# GB202-CC-from-SF-Base.net
KiCad netlist of a schematic drawn in EAGLE
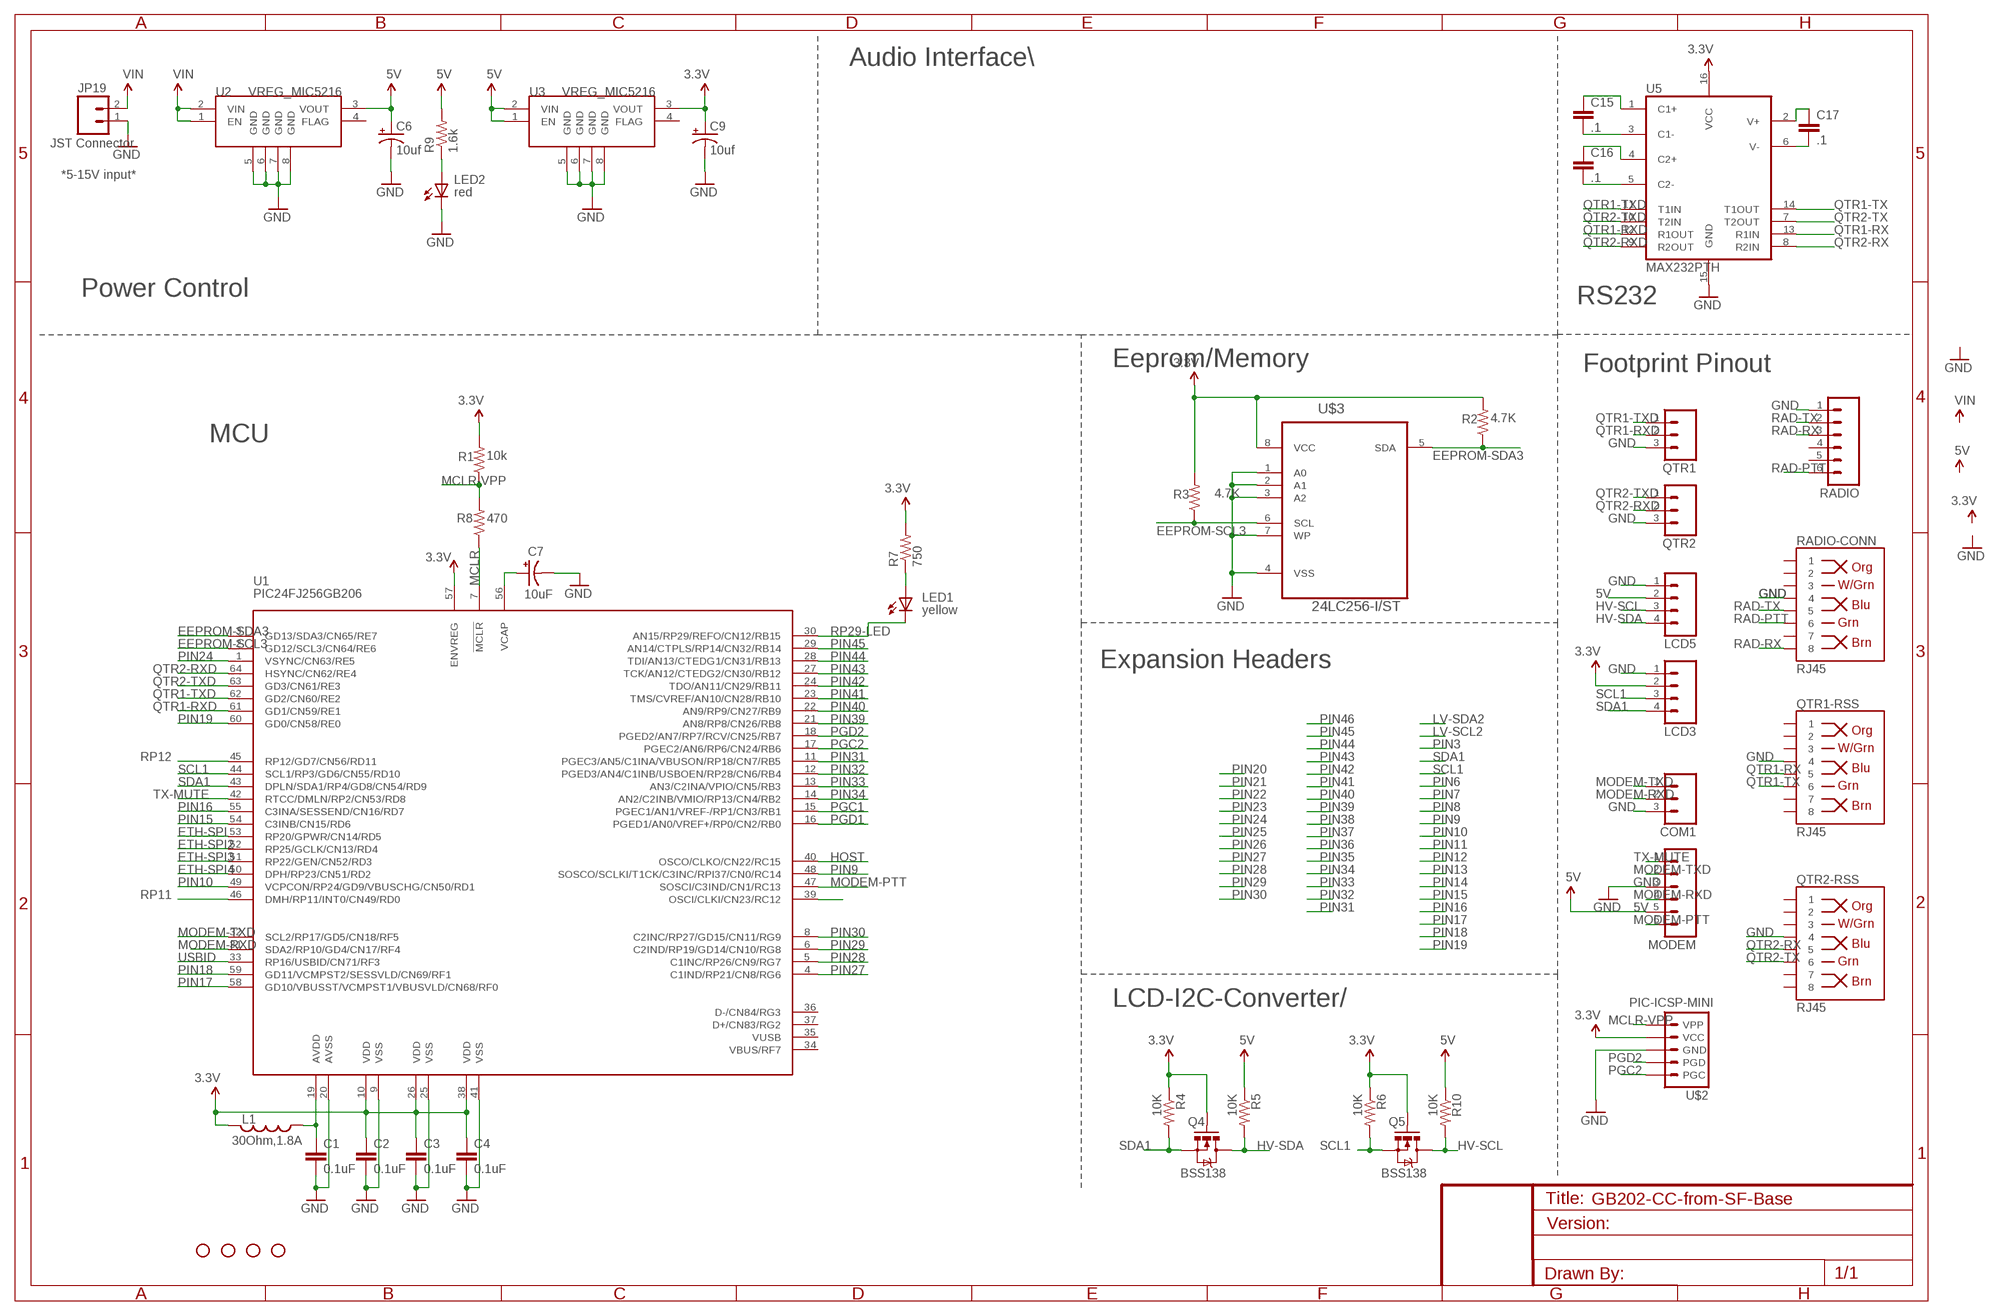
[diagram p0: schematic, sheet 1]

(export (version "E")
  (design (tool "Eeschema 10.0.6"))
  (components
    (comp (ref "C1")
      (value "0.1uF")
      (footprint "eagle-import:0603-CAP")
      (libsource (lib "eagle-import") (part "CAP0603-CAP"))
    )
    (comp (ref "C2")
      (value "0.1uF")
      (footprint "eagle-import:0402-CAP")
      (libsource (lib "eagle-import") (part "CAP0402-CAP"))
    )
    (comp (ref "C3")
      (value "0.1uF")
      (footprint "eagle-import:0603-CAP")
      (libsource (lib "eagle-import") (part "CAP0603-CAP"))
    )
    (comp (ref "C4")
      (value "0.1uF")
      (footprint "eagle-import:0402-CAP")
      (libsource (lib "eagle-import") (part "CAP0402-CAP"))
    )
    (comp (ref "C6")
      (value "10uf")
      (footprint "eagle-import:EIA3216")
      (libsource (lib "eagle-import") (part "SparkFun-Capacitors_CAP_POL1206"))
    )
    (comp (ref "C7")
      (value "10uF")
      (footprint "eagle-import:EIA3216")
      (libsource (lib "eagle-import") (part "CAP_POL1206"))
    )
    (comp (ref "C9")
      (value "10uf")
      (footprint "eagle-import:EIA3216")
      (libsource (lib "eagle-import") (part "SparkFun-Capacitors_CAP_POL1206"))
    )
    (comp (ref "C15")
      (value ".1")
      (footprint "eagle-import:CAP-PTH-SMALL")
      (libsource (lib "eagle-import") (part "CAPPTH"))
    )
    (comp (ref "C16")
      (value ".1")
      (footprint "eagle-import:CAP-PTH-SMALL")
      (libsource (lib "eagle-import") (part "CAPPTH"))
    )
    (comp (ref "C17")
      (value ".1")
      (footprint "eagle-import:CAP-PTH-SMALL")
      (libsource (lib "eagle-import") (part "CAPPTH"))
    )
    (comp (ref "COM1")
      (value "M031X03_NO_SILK")
      (footprint "eagle-import:1X03_NO_SILK")
      (libsource (lib "eagle-import") (part "M031X03_NO_SILK"))
    )
    (comp (ref "JP10")
      (value "STAND-OFF")
      (footprint "eagle-import:STAND-OFF")
      (libsource (lib "eagle-import") (part "STAND-OFF"))
    )
    (comp (ref "JP11")
      (value "STAND-OFF")
      (footprint "eagle-import:STAND-OFF")
      (libsource (lib "eagle-import") (part "STAND-OFF"))
    )
    (comp (ref "JP12")
      (value "STAND-OFF")
      (footprint "eagle-import:STAND-OFF")
      (libsource (lib "eagle-import") (part "STAND-OFF"))
    )
    (comp (ref "JP13")
      (value "STAND-OFF")
      (footprint "eagle-import:STAND-OFF")
      (libsource (lib "eagle-import") (part "STAND-OFF"))
    )
    (comp (ref "JP19")
      (value "JST Connector")
      (footprint "eagle-import:JST-2-SMD")
      (libsource (lib "eagle-import") (part "M02-JST-2MM-SMT"))
    )
    (comp (ref "L1")
      (value "30Ohm,1.8A")
      (footprint "eagle-import:0603")
      (libsource (lib "eagle-import") (part "INDUCTOR0603"))
    )
    (comp (ref "LCD3")
      (value "M04LONGPADS")
      (footprint "eagle-import:1X04_LONGPADS")
      (libsource (lib "eagle-import") (part "M04LONGPADS"))
    )
    (comp (ref "LCD5")
      (value "M04LONGPADS")
      (footprint "eagle-import:1X04_LONGPADS")
      (libsource (lib "eagle-import") (part "M04LONGPADS"))
    )
    (comp (ref "LED1")
      (value "LY L29K-J1K2-26-Z")
      (footprint "eagle-import:LED-0603")
      (libsource (lib "eagle-import") (part "SparkFun-LED_LED0603"))
    )
    (comp (ref "LED2")
      (value "LS L29K-G1J2-1-Z")
      (footprint "eagle-import:LED-0603")
      (libsource (lib "eagle-import") (part "LED0603"))
    )
    (comp (ref "MODEM")
      (value "M06LONGPADS")
      (footprint "eagle-import:1X06_LONGPADS")
      (libsource (lib "eagle-import") (part "M06LONGPADS"))
    )
    (comp (ref "Q4")
      (value "BSS138")
      (footprint "eagle-import:SOT23-3")
      (libsource (lib "eagle-import") (part "MOSFET-NCHANNELSMD"))
    )
    (comp (ref "Q5")
      (value "BSS138")
      (footprint "eagle-import:SOT23-3")
      (libsource (lib "eagle-import") (part "MOSFET-NCHANNELSMD"))
    )
    (comp (ref "QTR1")
      (value "M031X03_NO_SILK")
      (footprint "eagle-import:1X03_NO_SILK")
      (libsource (lib "eagle-import") (part "M031X03_NO_SILK"))
    )
    (comp (ref "QTR1-RSS")
      (value "RJ45")
      (footprint "eagle-import:RJ45-8")
      (libsource (lib "eagle-import") (part "RJ45-8PTH"))
    )
    (comp (ref "QTR2")
      (value "M031X03_NO_SILK")
      (footprint "eagle-import:1X03_NO_SILK")
      (libsource (lib "eagle-import") (part "M031X03_NO_SILK"))
    )
    (comp (ref "QTR2-RSS")
      (value "RJ45")
      (footprint "eagle-import:RJ45-8")
      (libsource (lib "eagle-import") (part "RJ45-8PTH"))
    )
    (comp (ref "R1")
      (value "10k")
      (footprint "eagle-import:0603-RES")
      (libsource (lib "eagle-import") (part "SparkFun-Resistors_RESISTOR0603-RES"))
    )
    (comp (ref "R2")
      (value "4.7K")
      (footprint "eagle-import:R0402")
      (libsource (lib "eagle-import") (part "R-US_R0402"))
    )
    (comp (ref "R3")
      (value "4.7K")
      (footprint "eagle-import:R0402")
      (libsource (lib "eagle-import") (part "R-US_R0402"))
    )
    (comp (ref "R4")
      (value "10K")
      (footprint "eagle-import:0402-RES")
      (libsource (lib "eagle-import") (part "RESISTOR0402-RES"))
    )
    (comp (ref "R5")
      (value "10K")
      (footprint "eagle-import:0603-RES")
      (libsource (lib "eagle-import") (part "RESISTOR0603-RES"))
    )
    (comp (ref "R6")
      (value "10K")
      (footprint "eagle-import:0402-RES")
      (libsource (lib "eagle-import") (part "RESISTOR0402-RES"))
    )
    (comp (ref "R7")
      (value "750")
      (footprint "eagle-import:0603-RES")
      (libsource (lib "eagle-import") (part "SparkFun-Resistors_RESISTOR0603-RES"))
    )
    (comp (ref "R8")
      (value "470")
      (footprint "eagle-import:0603-RES")
      (libsource (lib "eagle-import") (part "RESISTOR0603"))
    )
    (comp (ref "R9")
      (value "1.6k")
      (footprint "eagle-import:0603-RES")
      (libsource (lib "eagle-import") (part "SparkFun-Resistors_RESISTOR0603-RES"))
    )
    (comp (ref "R10")
      (value "10K")
      (footprint "eagle-import:0603-RES")
      (libsource (lib "eagle-import") (part "RESISTOR0603-RES"))
    )
    (comp (ref "RADIO")
      (value "M06LONGPADS")
      (footprint "eagle-import:1X06_LONGPADS")
      (libsource (lib "eagle-import") (part "M06LONGPADS"))
    )
    (comp (ref "RADIO-CONN")
      (value "RJ45")
      (footprint "eagle-import:RJ45-8")
      (libsource (lib "eagle-import") (part "RJ45-8PTH"))
    )
    (comp (ref "U$2")
      (value "PIC-ICSP-MINI")
      (footprint "eagle-import:PIC-ICSP-MINI")
      (libsource (lib "eagle-import") (part "PIC-ICSP-MINI"))
    )
    (comp (ref "U$3")
      (value "24LC256-I/ST")
      (footprint "eagle-import:SOP65P638X110-8N")
      (libsource (lib "eagle-import") (part "24LC256-I/ST"))
    )
    (comp (ref "U1")
      (value "PIC24FJ256GB206")
      (footprint "eagle-import:PIC24FXXX_TQFP64")
      (libsource (lib "eagle-import") (part "PIC24FXXXDAX06"))
    )
    (comp (ref "U2")
      (value "VREG_MIC5216")
      (footprint "eagle-import:MSOP8")
      (libsource (lib "eagle-import") (part "VREG_MIC5216"))
    )
    (comp (ref "U3")
      (value "VREG_MIC5216")
      (footprint "eagle-import:MSOP8")
      (libsource (lib "eagle-import") (part "VREG_MIC5216"))
    )
    (comp (ref "U5")
      (value "MAX232PTH")
      (footprint "eagle-import:DIL16")
      (libsource (lib "eagle-import") (part "MAX232PTH"))
    )
  )
  (nets
    (net (code "1") (name "/EEPROM-SCL3") (class "Default")
      (node (ref "R3") (pin "1") (pinfunction "1_1") (pintype "passive"))
      (node (ref "U$3") (pin "6") (pinfunction "SCL_6") (pintype "input"))
      (node (ref "U1") (pin "2") (pinfunction "GD12/SCL3/CN64/RE6_2") (pintype "bidirectional"))
    )
    (net (code "2") (name "/EEPROM-SDA3") (class "Default")
      (node (ref "R2") (pin "1") (pinfunction "1_1") (pintype "passive"))
      (node (ref "U$3") (pin "5") (pinfunction "SDA_5") (pintype "bidirectional"))
      (node (ref "U1") (pin "3") (pinfunction "GD13/SDA3/CN65/RE7_3") (pintype "bidirectional"))
    )
    (net (code "3") (name "/ETH-SPI") (class "Default")
      (node (ref "U1") (pin "53") (pinfunction "RP20/GPWR/CN14/RD5_53") (pintype "bidirectional"))
    )
    (net (code "4") (name "/ETH-SPI2") (class "Default")
      (node (ref "U1") (pin "52") (pinfunction "RP25/GCLK/CN13/RD4_52") (pintype "bidirectional"))
    )
    (net (code "5") (name "/ETH-SPI3") (class "Default")
      (node (ref "U1") (pin "51") (pinfunction "RP22/GEN/CN52/RD3_51") (pintype "bidirectional"))
    )
    (net (code "6") (name "/ETH-SPI4") (class "Default")
      (node (ref "U1") (pin "50") (pinfunction "DPH/RP23/CN51/RD2_50") (pintype "bidirectional"))
    )
    (net (code "7") (name "/HOST") (class "Default")
      (node (ref "U1") (pin "40") (pinfunction "OSCO/CLKO/CN22/RC15_40") (pintype "bidirectional"))
    )
    (net (code "8") (name "/HV-SCL") (class "Default")
      (node (ref "LCD5") (pin "3") (pinfunction "3_3") (pintype "passive"))
      (node (ref "Q5") (pin "3") (pinfunction "D_3") (pintype "passive"))
      (node (ref "R10") (pin "2") (pinfunction "2_2") (pintype "passive"))
    )
    (net (code "9") (name "/HV-SDA") (class "Default")
      (node (ref "LCD5") (pin "4") (pinfunction "4_4") (pintype "passive"))
      (node (ref "Q4") (pin "3") (pinfunction "D_3") (pintype "passive"))
      (node (ref "R5") (pin "2") (pinfunction "2_2") (pintype "passive"))
    )
    (net (code "12") (name "/MCLR") (class "Default")
      (node (ref "R8") (pin "1") (pinfunction "1_1") (pintype "passive"))
      (node (ref "U1") (pin "7") (pinfunction "~{MCLR}_7") (pintype "input"))
    )
    (net (code "13") (name "/MCLR-VPP") (class "Default")
      (node (ref "R1") (pin "1") (pinfunction "1_1") (pintype "passive"))
      (node (ref "R8") (pin "2") (pinfunction "2_2") (pintype "passive"))
      (node (ref "U$2") (pin "1") (pinfunction "VPP_1") (pintype "passive"))
    )
    (net (code "14") (name "/MODEM-PTT") (class "Default")
      (node (ref "MODEM") (pin "6") (pinfunction "6_6") (pintype "passive"))
      (node (ref "U1") (pin "47") (pinfunction "SOSCI/C3IND/CN1/RC13_47") (pintype "bidirectional"))
    )
    (net (code "15") (name "/MODEM-RXD") (class "Default")
      (node (ref "COM1") (pin "2") (pinfunction "2_2") (pintype "passive"))
      (node (ref "MODEM") (pin "4") (pinfunction "4_4") (pintype "passive"))
      (node (ref "U1") (pin "31") (pinfunction "SDA2/RP10/GD4/CN17/RF4_31") (pintype "bidirectional"))
    )
    (net (code "16") (name "/MODEM-TXD") (class "Default")
      (node (ref "COM1") (pin "1") (pinfunction "1_1") (pintype "passive"))
      (node (ref "MODEM") (pin "2") (pinfunction "2_2") (pintype "passive"))
      (node (ref "U1") (pin "32") (pinfunction "SCL2/RP17/GD5/CN18/RF5_32") (pintype "bidirectional"))
    )
    (net (code "17") (name "/PGC1") (class "Default")
      (node (ref "U1") (pin "15") (pinfunction "PGEC1/AN1/VREF-/RP1/CN3/RB1_15") (pintype "bidirectional"))
    )
    (net (code "18") (name "/PGC2") (class "Default")
      (node (ref "U$2") (pin "5") (pinfunction "PGC_5") (pintype "passive"))
      (node (ref "U1") (pin "17") (pinfunction "PGEC2/AN6/RP6/CN24/RB6_17") (pintype "bidirectional"))
    )
    (net (code "19") (name "/PGD1") (class "Default")
      (node (ref "U1") (pin "16") (pinfunction "PGED1/AN0/VREF+/RP0/CN2/RB0_16") (pintype "bidirectional"))
    )
    (net (code "20") (name "/PGD2") (class "Default")
      (node (ref "U$2") (pin "4") (pinfunction "PGD_4") (pintype "passive"))
      (node (ref "U1") (pin "18") (pinfunction "PGED2/AN7/RP7/RCV/CN25/RB7_18") (pintype "bidirectional"))
    )
    (net (code "25") (name "/PIN9") (class "Default")
      (node (ref "U1") (pin "48") (pinfunction "SOSCO/SCLKI/T1CK/C3INC/RPI37/CN0/RC14_48") (pintype "bidirectional"))
    )
    (net (code "26") (name "/PIN10") (class "Default")
      (node (ref "U1") (pin "49") (pinfunction "VCPCON/RP24/GD9/VBUSCHG/CN50/RD1_49") (pintype "bidirectional"))
    )
    (net (code "31") (name "/PIN15") (class "Default")
      (node (ref "U1") (pin "54") (pinfunction "C3INB/CN15/RD6_54") (pintype "bidirectional"))
    )
    (net (code "32") (name "/PIN16") (class "Default")
      (node (ref "U1") (pin "55") (pinfunction "C3INA/SESSEND/CN16/RD7_55") (pintype "bidirectional"))
    )
    (net (code "33") (name "/PIN17") (class "Default")
      (node (ref "U1") (pin "58") (pinfunction "GD10/VBUSST/VCMPST1/VBUSVLD/CN68/RF0_58") (pintype "bidirectional"))
    )
    (net (code "34") (name "/PIN18") (class "Default")
      (node (ref "U1") (pin "59") (pinfunction "GD11/VCMPST2/SESSVLD/CN69/RF1_59") (pintype "bidirectional"))
    )
    (net (code "35") (name "/PIN19") (class "Default")
      (node (ref "U1") (pin "60") (pinfunction "GD0/CN58/RE0_60") (pintype "bidirectional"))
    )
    (net (code "40") (name "/PIN24") (class "Default")
      (node (ref "U1") (pin "1") (pinfunction "VSYNC/CN63/RE5_1") (pintype "bidirectional"))
    )
    (net (code "43") (name "/PIN27") (class "Default")
      (node (ref "U1") (pin "4") (pinfunction "C1IND/RP21/CN8/RG6_4") (pintype "bidirectional"))
    )
    (net (code "44") (name "/PIN28") (class "Default")
      (node (ref "U1") (pin "5") (pinfunction "C1INC/RP26/CN9/RG7_5") (pintype "bidirectional"))
    )
    (net (code "45") (name "/PIN29") (class "Default")
      (node (ref "U1") (pin "6") (pinfunction "C2IND/RP19/GD14/CN10/RG8_6") (pintype "bidirectional"))
    )
    (net (code "46") (name "/PIN30") (class "Default")
      (node (ref "U1") (pin "8") (pinfunction "C2INC/RP27/GD15/CN11/RG9_8") (pintype "bidirectional"))
    )
    (net (code "47") (name "/PIN31") (class "Default")
      (node (ref "U1") (pin "11") (pinfunction "PGEC3/AN5/C1INA/VBUSON/RP18/CN7/RB5_11") (pintype "bidirectional"))
    )
    (net (code "48") (name "/PIN32") (class "Default")
      (node (ref "U1") (pin "12") (pinfunction "PGED3/AN4/C1INB/USBOEN/RP28/CN6/RB4_12") (pintype "bidirectional"))
    )
    (net (code "49") (name "/PIN33") (class "Default")
      (node (ref "U1") (pin "13") (pinfunction "AN3/C2INA/VPIO/CN5/RB3_13") (pintype "bidirectional"))
    )
    (net (code "50") (name "/PIN34") (class "Default")
      (node (ref "U1") (pin "14") (pinfunction "AN2/C2INB/VMIO/RP13/CN4/RB2_14") (pintype "bidirectional"))
    )
    (net (code "55") (name "/PIN39") (class "Default")
      (node (ref "U1") (pin "21") (pinfunction "AN8/RP8/CN26/RB8_21") (pintype "bidirectional"))
    )
    (net (code "56") (name "/PIN40") (class "Default")
      (node (ref "U1") (pin "22") (pinfunction "AN9/RP9/CN27/RB9_22") (pintype "bidirectional"))
    )
    (net (code "57") (name "/PIN41") (class "Default")
      (node (ref "U1") (pin "23") (pinfunction "TMS/CVREF/AN10/CN28/RB10_23") (pintype "bidirectional"))
    )
    (net (code "58") (name "/PIN42") (class "Default")
      (node (ref "U1") (pin "24") (pinfunction "TDO/AN11/CN29/RB11_24") (pintype "bidirectional"))
    )
    (net (code "59") (name "/PIN43") (class "Default")
      (node (ref "U1") (pin "27") (pinfunction "TCK/AN12/CTEDG2/CN30/RB12_27") (pintype "bidirectional"))
    )
    (net (code "60") (name "/PIN44") (class "Default")
      (node (ref "U1") (pin "28") (pinfunction "TDI/AN13/CTEDG1/CN31/RB13_28") (pintype "bidirectional"))
    )
    (net (code "61") (name "/PIN45") (class "Default")
      (node (ref "U1") (pin "29") (pinfunction "AN14/CTPLS/RP14/CN32/RB14_29") (pintype "bidirectional"))
    )
    (net (code "63") (name "/QTR1-RX") (class "Default")
      (node (ref "QTR1-RSS") (pin "5") (pinfunction "5_5") (pintype "bidirectional"))
      (node (ref "U5") (pin "13") (pinfunction "R1IN_13") (pintype "input"))
    )
    (net (code "64") (name "/QTR1-RXD") (class "Default")
      (node (ref "QTR1") (pin "2") (pinfunction "2_2") (pintype "passive"))
      (node (ref "U1") (pin "61") (pinfunction "GD1/CN59/RE1_61") (pintype "bidirectional"))
      (node (ref "U5") (pin "12") (pinfunction "R1OUT_12") (pintype "output"))
    )
    (net (code "65") (name "/QTR1-TX") (class "Default")
      (node (ref "QTR1-RSS") (pin "6") (pinfunction "6_6") (pintype "bidirectional"))
      (node (ref "U5") (pin "14") (pinfunction "T1OUT_14") (pintype "output"))
    )
    (net (code "66") (name "/QTR1-TXD") (class "Default")
      (node (ref "QTR1") (pin "1") (pinfunction "1_1") (pintype "passive"))
      (node (ref "U1") (pin "62") (pinfunction "GD2/CN60/RE2_62") (pintype "bidirectional"))
      (node (ref "U5") (pin "11") (pinfunction "T1IN_11") (pintype "input"))
    )
    (net (code "67") (name "/QTR2-RX") (class "Default")
      (node (ref "QTR2-RSS") (pin "5") (pinfunction "5_5") (pintype "bidirectional"))
      (node (ref "U5") (pin "8") (pinfunction "R2IN_8") (pintype "input"))
    )
    (net (code "68") (name "/QTR2-RXD") (class "Default")
      (node (ref "QTR2") (pin "2") (pinfunction "2_2") (pintype "passive"))
      (node (ref "U1") (pin "64") (pinfunction "HSYNC/CN62/RE4_64") (pintype "bidirectional"))
      (node (ref "U5") (pin "9") (pinfunction "R2OUT_9") (pintype "output"))
    )
    (net (code "69") (name "/QTR2-TX") (class "Default")
      (node (ref "QTR2-RSS") (pin "6") (pinfunction "6_6") (pintype "bidirectional"))
      (node (ref "U5") (pin "7") (pinfunction "T2OUT_7") (pintype "output"))
    )
    (net (code "70") (name "/QTR2-TXD") (class "Default")
      (node (ref "QTR2") (pin "1") (pinfunction "1_1") (pintype "passive"))
      (node (ref "U1") (pin "63") (pinfunction "GD3/CN61/RE3_63") (pintype "bidirectional"))
      (node (ref "U5") (pin "10") (pinfunction "T2IN_10") (pintype "input"))
    )
    (net (code "71") (name "/RAD-PTT") (class "Default")
      (node (ref "RADIO") (pin "6") (pinfunction "6_6") (pintype "passive"))
      (node (ref "RADIO-CONN") (pin "6") (pinfunction "6_6") (pintype "bidirectional"))
    )
    (net (code "72") (name "/RAD-RX") (class "Default")
      (node (ref "RADIO") (pin "3") (pinfunction "3_3") (pintype "passive"))
      (node (ref "RADIO-CONN") (pin "8") (pinfunction "8_8") (pintype "bidirectional"))
    )
    (net (code "73") (name "/RAD-TX") (class "Default")
      (node (ref "RADIO") (pin "2") (pinfunction "2_2") (pintype "passive"))
      (node (ref "RADIO-CONN") (pin "5") (pinfunction "5_5") (pintype "bidirectional"))
    )
    (net (code "74") (name "/RP11") (class "Default")
      (node (ref "U1") (pin "46") (pinfunction "DMH/RP11/INT0/CN49/RD0_46") (pintype "bidirectional"))
    )
    (net (code "75") (name "/RP12") (class "Default")
      (node (ref "U1") (pin "45") (pinfunction "RP12/GD7/CN56/RD11_45") (pintype "bidirectional"))
    )
    (net (code "76") (name "/RP29-LED") (class "Default")
      (node (ref "LED1") (pin "C") (pinfunction "C_C") (pintype "passive"))
      (node (ref "U1") (pin "30") (pinfunction "AN15/RP29/REFO/CN12/RB15_30") (pintype "bidirectional"))
    )
    (net (code "77") (name "/SCL1") (class "Default")
      (node (ref "LCD3") (pin "3") (pinfunction "3_3") (pintype "passive"))
      (node (ref "Q5") (pin "2") (pinfunction "S_2") (pintype "passive"))
      (node (ref "R6") (pin "2") (pinfunction "2_2") (pintype "passive"))
      (node (ref "U1") (pin "44") (pinfunction "SCL1/RP3/GD6/CN55/RD10_44") (pintype "bidirectional"))
    )
    (net (code "78") (name "/SDA1") (class "Default")
      (node (ref "LCD3") (pin "4") (pinfunction "4_4") (pintype "passive"))
      (node (ref "Q4") (pin "2") (pinfunction "S_2") (pintype "passive"))
      (node (ref "R4") (pin "2") (pinfunction "2_2") (pintype "passive"))
      (node (ref "U1") (pin "43") (pinfunction "DPLN/SDA1/RP4/GD8/CN54/RD9_43") (pintype "bidirectional"))
    )
    (net (code "79") (name "/TX-MUTE") (class "Default")
      (node (ref "MODEM") (pin "1") (pinfunction "1_1") (pintype "passive"))
      (node (ref "U1") (pin "42") (pinfunction "RTCC/DMLN/RP2/CN53/RD8_42") (pintype "bidirectional"))
    )
    (net (code "80") (name "/USBID") (class "Default")
      (node (ref "U1") (pin "33") (pinfunction "RP16/USBID/CN71/RF3_33") (pintype "bidirectional"))
    )
    (net (code "81") (name "/VUSB") (class "Default")
      (node (ref "U1") (pin "35") (pinfunction "VUSB_35") (pintype "power_in"))
    )
    (net (code "82") (name "3.3V") (class "Default")
      (node (ref "C2") (pin "1") (pinfunction "1_1") (pintype "passive"))
      (node (ref "C3") (pin "1") (pinfunction "1_1") (pintype "passive"))
      (node (ref "C4") (pin "1") (pinfunction "1_1") (pintype "passive"))
      (node (ref "C9") (pin "A") (pinfunction "+_A") (pintype "passive"))
      (node (ref "L1") (pin "2") (pinfunction "2_2") (pintype "passive"))
      (node (ref "LCD3") (pin "2") (pinfunction "2_2") (pintype "passive"))
      (node (ref "Q4") (pin "1") (pinfunction "G_1") (pintype "passive"))
      (node (ref "Q5") (pin "1") (pinfunction "G_1") (pintype "passive"))
      (node (ref "R1") (pin "2") (pinfunction "2_2") (pintype "passive"))
      (node (ref "R2") (pin "2") (pinfunction "2_2") (pintype "passive"))
      (node (ref "R3") (pin "2") (pinfunction "2_2") (pintype "passive"))
      (node (ref "R4") (pin "1") (pinfunction "1_1") (pintype "passive"))
      (node (ref "R6") (pin "1") (pinfunction "1_1") (pintype "passive"))
      (node (ref "R7") (pin "2") (pinfunction "2_2") (pintype "passive"))
      (node (ref "U$2") (pin "2") (pinfunction "VCC_2") (pintype "passive"))
      (node (ref "U$3") (pin "8") (pinfunction "VCC_8") (pintype "power_in"))
      (node (ref "U1") (pin "10") (pinfunction "VDD_10") (pintype "power_in"))
      (node (ref "U1") (pin "26") (pinfunction "VDD_26") (pintype "power_in"))
      (node (ref "U1") (pin "38") (pinfunction "VDD_38") (pintype "power_in"))
      (node (ref "U1") (pin "57") (pinfunction "ENVREG_57") (pintype "input"))
      (node (ref "U3") (pin "3") (pinfunction "VOUT_3") (pintype "bidirectional"))
      (node (ref "U5") (pin "16") (pinfunction "VCC_16") (pintype "bidirectional"))
    )
    (net (code "83") (name "5V") (class "Default")
      (node (ref "C6") (pin "A") (pinfunction "+_A") (pintype "passive"))
      (node (ref "LCD5") (pin "2") (pinfunction "2_2") (pintype "passive"))
      (node (ref "MODEM") (pin "5") (pinfunction "5_5") (pintype "passive"))
      (node (ref "R10") (pin "1") (pinfunction "1_1") (pintype "passive"))
      (node (ref "R5") (pin "1") (pinfunction "1_1") (pintype "passive"))
      (node (ref "R9") (pin "2") (pinfunction "2_2") (pintype "passive"))
      (node (ref "U2") (pin "3") (pinfunction "VOUT_3") (pintype "bidirectional"))
      (node (ref "U3") (pin "1") (pinfunction "EN_1") (pintype "bidirectional"))
      (node (ref "U3") (pin "2") (pinfunction "VIN_2") (pintype "bidirectional"))
    )
    (net (code "84") (name "GND") (class "Default")
      (node (ref "C1") (pin "2") (pinfunction "2_2") (pintype "passive"))
      (node (ref "C2") (pin "2") (pinfunction "2_2") (pintype "passive"))
      (node (ref "C3") (pin "2") (pinfunction "2_2") (pintype "passive"))
      (node (ref "C4") (pin "2") (pinfunction "2_2") (pintype "passive"))
      (node (ref "C6") (pin "C") (pinfunction "-_C") (pintype "passive"))
      (node (ref "C7") (pin "C") (pinfunction "-_C") (pintype "passive"))
      (node (ref "C9") (pin "C") (pinfunction "-_C") (pintype "passive"))
      (node (ref "COM1") (pin "3") (pinfunction "3_3") (pintype "passive"))
      (node (ref "JP19") (pin "1") (pinfunction "1_1") (pintype "passive"))
      (node (ref "LCD3") (pin "1") (pinfunction "1_1") (pintype "passive"))
      (node (ref "LCD5") (pin "1") (pinfunction "1_1") (pintype "passive"))
      (node (ref "LED2") (pin "C") (pinfunction "C_C") (pintype "passive"))
      (node (ref "MODEM") (pin "3") (pinfunction "3_3") (pintype "passive"))
      (node (ref "QTR1") (pin "3") (pinfunction "3_3") (pintype "passive"))
      (node (ref "QTR1-RSS") (pin "4") (pinfunction "4_4") (pintype "bidirectional"))
      (node (ref "QTR2") (pin "3") (pinfunction "3_3") (pintype "passive"))
      (node (ref "QTR2-RSS") (pin "4") (pinfunction "4_4") (pintype "bidirectional"))
      (node (ref "RADIO") (pin "1") (pinfunction "1_1") (pintype "passive"))
      (node (ref "RADIO-CONN") (pin "4") (pinfunction "4_4") (pintype "bidirectional"))
      (node (ref "U$2") (pin "3") (pinfunction "GND_3") (pintype "passive"))
      (node (ref "U$3") (pin "1") (pinfunction "A0_1") (pintype "input"))
      (node (ref "U$3") (pin "2") (pinfunction "A1_2") (pintype "input"))
      (node (ref "U$3") (pin "3") (pinfunction "A2_3") (pintype "input"))
      (node (ref "U$3") (pin "4") (pinfunction "VSS_4") (pintype "passive"))
      (node (ref "U$3") (pin "7") (pinfunction "WP_7") (pintype "input"))
      (node (ref "U1") (pin "20") (pinfunction "AVSS_20") (pintype "power_in"))
      (node (ref "U1") (pin "25") (pinfunction "VSS_25") (pintype "power_in"))
      (node (ref "U1") (pin "41") (pinfunction "VSS_41") (pintype "power_in"))
      (node (ref "U1") (pin "9") (pinfunction "VSS_9") (pintype "power_in"))
      (node (ref "U2") (pin "5") (pinfunction "GND_5") (pintype "bidirectional"))
      (node (ref "U2") (pin "6") (pinfunction "GND_6") (pintype "bidirectional"))
      (node (ref "U2") (pin "7") (pinfunction "GND_7") (pintype "bidirectional"))
      (node (ref "U2") (pin "8") (pinfunction "GND_8") (pintype "bidirectional"))
      (node (ref "U3") (pin "5") (pinfunction "GND_5") (pintype "bidirectional"))
      (node (ref "U3") (pin "6") (pinfunction "GND_6") (pintype "bidirectional"))
      (node (ref "U3") (pin "7") (pinfunction "GND_7") (pintype "bidirectional"))
      (node (ref "U3") (pin "8") (pinfunction "GND_8") (pintype "bidirectional"))
      (node (ref "U5") (pin "15") (pinfunction "GND_15") (pintype "bidirectional"))
    )
    (net (code "85") (name "Net-(C7-+)") (class "Default")
      (node (ref "C7") (pin "A") (pinfunction "+_A") (pintype "passive"))
      (node (ref "U1") (pin "56") (pinfunction "VCAP_56") (pintype "power_in"))
    )
    (net (code "86") (name "Net-(LED1-PadA)") (class "Default")
      (node (ref "LED1") (pin "A") (pinfunction "A_A") (pintype "passive"))
      (node (ref "R7") (pin "1") (pinfunction "1_1") (pintype "passive"))
    )
    (net (code "87") (name "Net-(LED2-PadA)") (class "Default")
      (node (ref "LED2") (pin "A") (pinfunction "A_A") (pintype "passive"))
      (node (ref "R9") (pin "1") (pinfunction "1_1") (pintype "passive"))
    )
    (net (code "88") (name "Net-(U1-AVDD)") (class "Default")
      (node (ref "C1") (pin "1") (pinfunction "1_1") (pintype "passive"))
      (node (ref "L1") (pin "1") (pinfunction "1_1") (pintype "passive"))
      (node (ref "U1") (pin "19") (pinfunction "AVDD_19") (pintype "power_in"))
    )
    (net (code "89") (name "Net-(U5-C1+)") (class "Default")
      (node (ref "C15") (pin "1") (pinfunction "1_1") (pintype "passive"))
      (node (ref "U5") (pin "1") (pinfunction "C1+_1") (pintype "bidirectional"))
    )
    (net (code "90") (name "Net-(U5-C1-)") (class "Default")
      (node (ref "C15") (pin "2") (pinfunction "2_2") (pintype "passive"))
      (node (ref "U5") (pin "3") (pinfunction "C1-_3") (pintype "bidirectional"))
    )
    (net (code "91") (name "Net-(U5-C2+)") (class "Default")
      (node (ref "C16") (pin "1") (pinfunction "1_1") (pintype "passive"))
      (node (ref "U5") (pin "4") (pinfunction "C2+_4") (pintype "bidirectional"))
    )
    (net (code "92") (name "Net-(U5-C2-)") (class "Default")
      (node (ref "C16") (pin "2") (pinfunction "2_2") (pintype "passive"))
      (node (ref "U5") (pin "5") (pinfunction "C2-_5") (pintype "bidirectional"))
    )
    (net (code "93") (name "Net-(U5-V+)") (class "Default")
      (node (ref "C17") (pin "1") (pinfunction "1_1") (pintype "passive"))
      (node (ref "U5") (pin "2") (pinfunction "V+_2") (pintype "bidirectional"))
    )
    (net (code "94") (name "Net-(U5-V-)") (class "Default")
      (node (ref "C17") (pin "2") (pinfunction "2_2") (pintype "passive"))
      (node (ref "U5") (pin "6") (pinfunction "V-_6") (pintype "bidirectional"))
    )
    (net (code "95") (name "VIN") (class "Default")
      (node (ref "JP19") (pin "2") (pinfunction "2_2") (pintype "passive"))
      (node (ref "U2") (pin "1") (pinfunction "EN_1") (pintype "bidirectional"))
      (node (ref "U2") (pin "2") (pinfunction "VIN_2") (pintype "bidirectional"))
    )
    (net (code "96") (name "unconnected-(QTR1-RSS-Pad1)") (class "Default")
      (node (ref "QTR1-RSS") (pin "1") (pinfunction "1_1") (pintype "bidirectional"))
    )
    (net (code "97") (name "unconnected-(QTR1-RSS-Pad2)") (class "Default")
      (node (ref "QTR1-RSS") (pin "2") (pinfunction "2_2") (pintype "bidirectional"))
    )
    (net (code "98") (name "unconnected-(QTR1-RSS-Pad3)") (class "Default")
      (node (ref "QTR1-RSS") (pin "3") (pinfunction "3_3") (pintype "bidirectional"))
    )
    (net (code "99") (name "unconnected-(QTR1-RSS-Pad7)") (class "Default")
      (node (ref "QTR1-RSS") (pin "7") (pinfunction "7_7") (pintype "bidirectional"))
    )
    (net (code "100") (name "unconnected-(QTR1-RSS-Pad8)") (class "Default")
      (node (ref "QTR1-RSS") (pin "8") (pinfunction "8_8") (pintype "bidirectional"))
    )
    (net (code "101") (name "unconnected-(QTR2-RSS-Pad1)") (class "Default")
      (node (ref "QTR2-RSS") (pin "1") (pinfunction "1_1") (pintype "bidirectional"))
    )
    (net (code "102") (name "unconnected-(QTR2-RSS-Pad2)") (class "Default")
      (node (ref "QTR2-RSS") (pin "2") (pinfunction "2_2") (pintype "bidirectional"))
    )
    (net (code "103") (name "unconnected-(QTR2-RSS-Pad3)") (class "Default")
      (node (ref "QTR2-RSS") (pin "3") (pinfunction "3_3") (pintype "bidirectional"))
    )
    (net (code "104") (name "unconnected-(QTR2-RSS-Pad7)") (class "Default")
      (node (ref "QTR2-RSS") (pin "7") (pinfunction "7_7") (pintype "bidirectional"))
    )
    (net (code "105") (name "unconnected-(QTR2-RSS-Pad8)") (class "Default")
      (node (ref "QTR2-RSS") (pin "8") (pinfunction "8_8") (pintype "bidirectional"))
    )
    (net (code "106") (name "unconnected-(RADIO-CONN-Pad1)") (class "Default")
      (node (ref "RADIO-CONN") (pin "1") (pinfunction "1_1") (pintype "bidirectional"))
    )
    (net (code "107") (name "unconnected-(RADIO-CONN-Pad2)") (class "Default")
      (node (ref "RADIO-CONN") (pin "2") (pinfunction "2_2") (pintype "bidirectional"))
    )
    (net (code "108") (name "unconnected-(RADIO-CONN-Pad3)") (class "Default")
      (node (ref "RADIO-CONN") (pin "3") (pinfunction "3_3") (pintype "bidirectional"))
    )
    (net (code "109") (name "unconnected-(RADIO-CONN-Pad7)") (class "Default")
      (node (ref "RADIO-CONN") (pin "7") (pinfunction "7_7") (pintype "bidirectional"))
    )
    (net (code "110") (name "unconnected-(RADIO-Pad4)") (class "Default")
      (node (ref "RADIO") (pin "4") (pinfunction "4_4") (pintype "passive"))
    )
    (net (code "111") (name "unconnected-(RADIO-Pad5)") (class "Default")
      (node (ref "RADIO") (pin "5") (pinfunction "5_5") (pintype "passive"))
    )
    (net (code "112") (name "unconnected-(U1-D+{slash}CN83{slash}RG2-Pad37)") (class "Default")
      (node (ref "U1") (pin "37") (pinfunction "D+/CN83/RG2_37") (pintype "bidirectional"))
    )
    (net (code "113") (name "unconnected-(U1-D-{slash}CN84{slash}RG3-Pad36)") (class "Default")
      (node (ref "U1") (pin "36") (pinfunction "D-/CN84/RG3_36") (pintype "bidirectional"))
    )
    (net (code "114") (name "unconnected-(U1-OSCI{slash}CLKI{slash}CN23{slash}RC12-Pad39)") (class "Default")
      (node (ref "U1") (pin "39") (pinfunction "OSCI/CLKI/CN23/RC12_39") (pintype "bidirectional"))
    )
    (net (code "115") (name "unconnected-(U1-VBUS{slash}RF7-Pad34)") (class "Default")
      (node (ref "U1") (pin "34") (pinfunction "VBUS/RF7_34") (pintype "input"))
    )
    (net (code "116") (name "unconnected-(U2-FLAG-Pad4)") (class "Default")
      (node (ref "U2") (pin "4") (pinfunction "FLAG_4") (pintype "bidirectional"))
    )
    (net (code "117") (name "unconnected-(U3-FLAG-Pad4)") (class "Default")
      (node (ref "U3") (pin "4") (pinfunction "FLAG_4") (pintype "bidirectional"))
    )
  )
)
